# BUZZER.net
KiCad netlist of a schematic drawn in Altium Designer
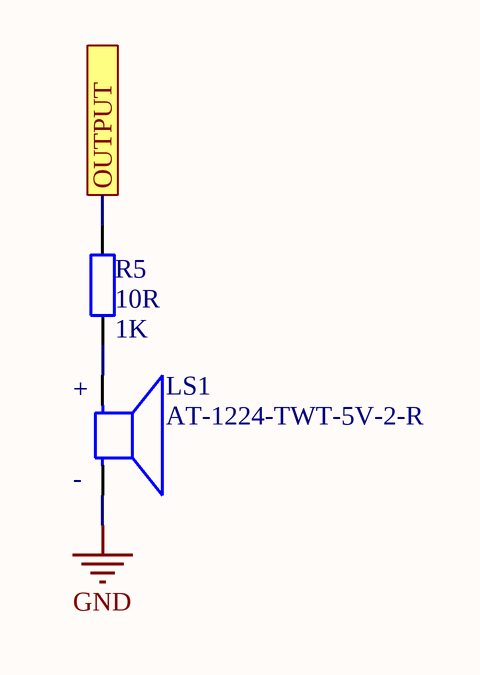
[diagram p0: BUZZER.SchDoc]

(export (version "E")
  (design (tool "Eeschema 10.0.6"))
  (components
    (comp (ref "LS1")
      (value "AT-1224-TWT-5V-2-R")
      (footprint "XDCR_AT-1224-TWT-5V-2-R")
      (description "AUDIO TRANSDUCER 12 VP-P 85 DB 2400 HZ")
      (libsource (lib "BUZZER") (part "AT-1224-TWT-5V-2-R"))
    )
    (comp (ref "R5")
      (value "10R")
      (footprint "AXIAL-0.4")
      (description "Resistor")
      (fields (field (name "ALTIUM_VALUE") "1K") (field (name "PUBLISHER") "Altium Limited"))
      (libsource (lib "Miscellaneous Devices") (part "Res2"))
    )
  )
  (nets
    (net (code "1") (name "/OUTPUT") (class "Default")
      (node (ref "R5") (pin "2") (pinfunction "2_2") (pintype "passive"))
    )
    (net (code "2") (name "GND") (class "Default")
      (node (ref "LS1") (pin "N") (pinfunction "N_N") (pintype "passive"))
    )
    (net (code "3") (name "Net-(LS1-PadP)") (class "Default")
      (node (ref "LS1") (pin "P") (pinfunction "P_P") (pintype "passive"))
      (node (ref "R5") (pin "1") (pinfunction "1_1") (pintype "passive"))
    )
  )
)
